# SensorHub.net
KiCad netlist of a schematic drawn in EAGLE
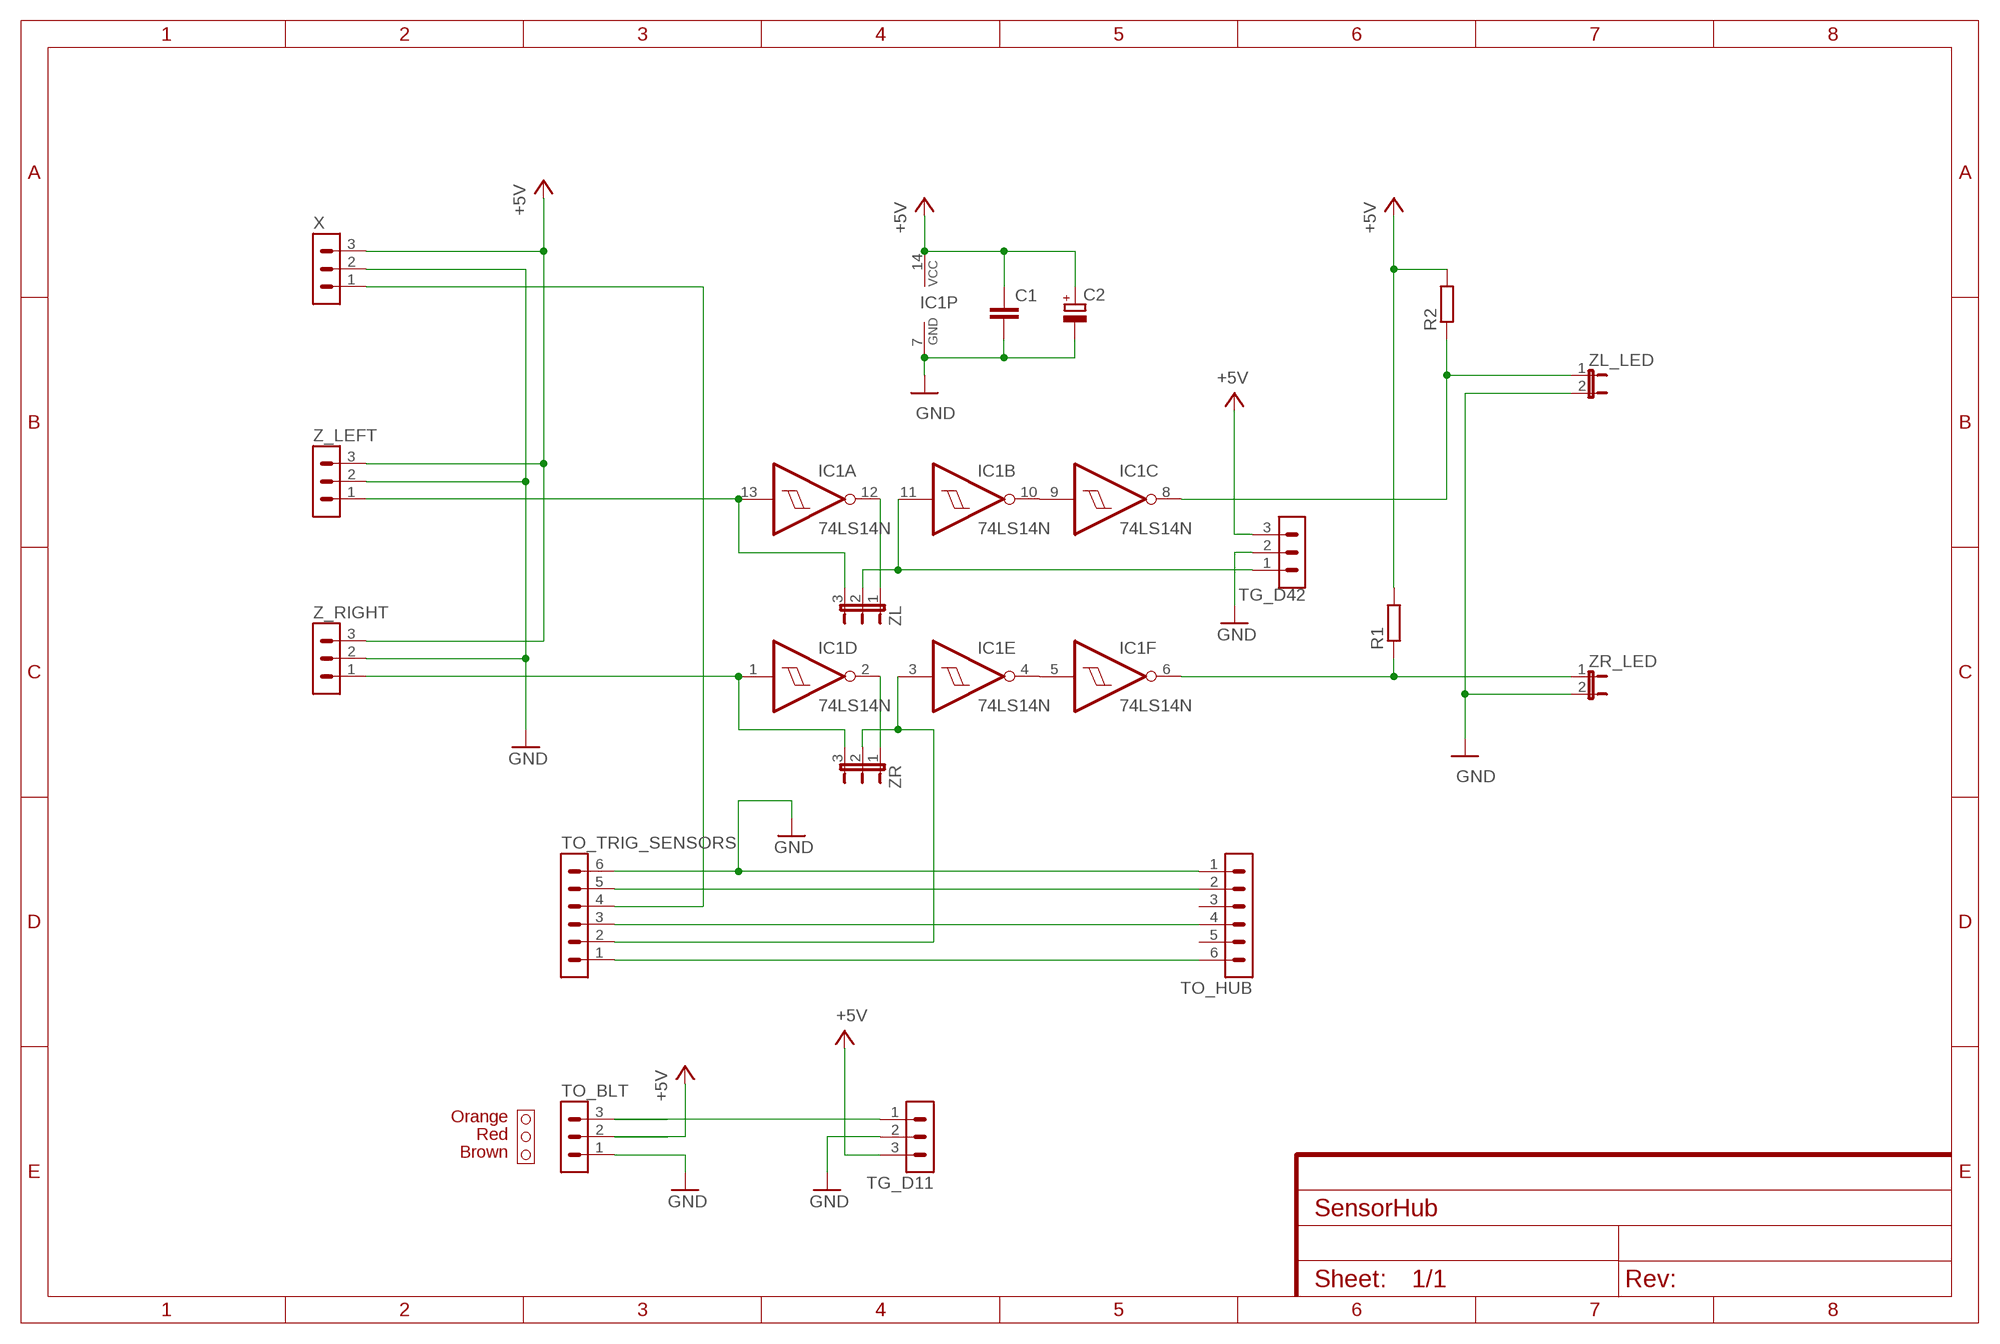
[diagram p0: schematic, sheet 1]

(export (version "E")
  (design (tool "Eeschema 10.0.6"))
  (components
    (comp (ref "C1")
      (value "C-EU050-030X075")
      (footprint "eagle-import:C050-030X075")
      (libsource (lib "eagle-import") (part "C-EU050-030X075"))
    )
    (comp (ref "C2")
      (value "CPOL-EUE3.5-8")
      (footprint "eagle-import:E3,5-8")
      (libsource (lib "eagle-import") (part "CPOL-EUE3.5-8"))
    )
    (comp (ref "IC1")
      (value "74LS14N")
      (footprint "eagle-import:DIL14")
      (libsource (lib "eagle-import") (part "7414NLS"))
    )
    (comp (ref "R1")
      (value "R-EU_0207/10")
      (footprint "eagle-import:0207_10")
      (libsource (lib "eagle-import") (part "R-EU_0207/10"))
    )
    (comp (ref "R2")
      (value "R-EU_0207/10")
      (footprint "eagle-import:0207_10")
      (libsource (lib "eagle-import") (part "R-EU_0207/10"))
    )
    (comp (ref "TG_D11")
      (value "JST-3PTOP")
      (footprint "eagle-import:XH-A-TOP-3P")
      (libsource (lib "eagle-import") (part "JST-3PTOP"))
    )
    (comp (ref "TG_D42")
      (value "JST-3PTOP")
      (footprint "eagle-import:XH-A-TOP-3P")
      (libsource (lib "eagle-import") (part "JST-3PTOP"))
    )
    (comp (ref "TO_BLT")
      (value "JST-3PTOP")
      (footprint "eagle-import:XH-A-TOP-3P")
      (libsource (lib "eagle-import") (part "JST-3PTOP"))
    )
    (comp (ref "TO_HUB")
      (value "JST-6PPH-TOP")
      (footprint "eagle-import:PH-TOP-6P")
      (libsource (lib "eagle-import") (part "JST-6PPH-TOP"))
    )
    (comp (ref "TO_TRIG_SENSORS")
      (value "JST-6PPH-TOP")
      (footprint "eagle-import:PH-TOP-6P")
      (libsource (lib "eagle-import") (part "JST-6PPH-TOP"))
    )
    (comp (ref "X")
      (value "JST-3PTOP")
      (footprint "eagle-import:XH-A-TOP-3P")
      (libsource (lib "eagle-import") (part "JST-3PTOP"))
    )
    (comp (ref "ZL")
      (value "JP2E")
      (footprint "eagle-import:JP2")
      (libsource (lib "eagle-import") (part "JP2E"))
    )
    (comp (ref "ZL_LED")
      (value "ZL LED")
      (footprint "eagle-import:JP1")
      (libsource (lib "eagle-import") (part "JP1E"))
    )
    (comp (ref "ZR")
      (value "JP2E")
      (footprint "eagle-import:JP2")
      (libsource (lib "eagle-import") (part "JP2E"))
    )
    (comp (ref "ZR_LED")
      (value "ZR LED")
      (footprint "eagle-import:JP1")
      (libsource (lib "eagle-import") (part "JP1E"))
    )
    (comp (ref "Z_LEFT")
      (value "JST-3PTOP")
      (footprint "eagle-import:XH-A-TOP-3P")
      (libsource (lib "eagle-import") (part "JST-3PTOP"))
    )
    (comp (ref "Z_RIGHT")
      (value "JST-3PTOP")
      (footprint "eagle-import:XH-A-TOP-3P")
      (libsource (lib "eagle-import") (part "JST-3PTOP"))
    )
  )
  (nets
    (net (code "1") (name "+5V") (class "Default")
      (node (ref "C1") (pin "1") (pinfunction "1_1") (pintype "passive"))
      (node (ref "C2") (pin "+") (pinfunction "+_+") (pintype "passive"))
      (node (ref "IC1") (pin "14") (pinfunction "VCC_14") (pintype "power_in"))
      (node (ref "R1") (pin "2") (pinfunction "2_2") (pintype "passive"))
      (node (ref "R2") (pin "2") (pinfunction "2_2") (pintype "passive"))
      (node (ref "TG_D11") (pin "3") (pinfunction "3_3") (pintype "bidirectional"))
      (node (ref "TG_D42") (pin "3") (pinfunction "3_3") (pintype "bidirectional"))
      (node (ref "TO_BLT") (pin "2") (pinfunction "2_2") (pintype "bidirectional"))
      (node (ref "X") (pin "3") (pinfunction "3_3") (pintype "bidirectional"))
      (node (ref "Z_LEFT") (pin "3") (pinfunction "3_3") (pintype "bidirectional"))
      (node (ref "Z_RIGHT") (pin "3") (pinfunction "3_3") (pintype "bidirectional"))
    )
    (net (code "2") (name "GND") (class "Default")
      (node (ref "C1") (pin "2") (pinfunction "2_2") (pintype "passive"))
      (node (ref "C2") (pin "-") (pinfunction "-_-") (pintype "passive"))
      (node (ref "IC1") (pin "7") (pinfunction "GND_7") (pintype "power_in"))
      (node (ref "TG_D11") (pin "2") (pinfunction "2_2") (pintype "bidirectional"))
      (node (ref "TG_D42") (pin "2") (pinfunction "2_2") (pintype "bidirectional"))
      (node (ref "TO_BLT") (pin "1") (pinfunction "1_1") (pintype "bidirectional"))
      (node (ref "TO_HUB") (pin "1") (pinfunction "1_1") (pintype "bidirectional"))
      (node (ref "TO_TRIG_SENSORS") (pin "6") (pinfunction "6_6") (pintype "bidirectional"))
      (node (ref "X") (pin "2") (pinfunction "2_2") (pintype "bidirectional"))
      (node (ref "ZL_LED") (pin "2") (pinfunction "2_2") (pintype "passive"))
      (node (ref "ZR_LED") (pin "2") (pinfunction "2_2") (pintype "passive"))
      (node (ref "Z_LEFT") (pin "2") (pinfunction "2_2") (pintype "bidirectional"))
      (node (ref "Z_RIGHT") (pin "2") (pinfunction "2_2") (pintype "bidirectional"))
    )
    (net (code "3") (name "Net-(IC1A-I)") (class "Default")
      (node (ref "IC1") (pin "13") (pinfunction "I_13") (pintype "input"))
      (node (ref "ZL") (pin "3") (pinfunction "3_3") (pintype "passive"))
      (node (ref "Z_LEFT") (pin "1") (pinfunction "1_1") (pintype "bidirectional"))
    )
    (net (code "4") (name "Net-(IC1A-O)") (class "Default")
      (node (ref "IC1") (pin "12") (pinfunction "O_12") (pintype "output"))
      (node (ref "ZL") (pin "1") (pinfunction "1_1") (pintype "passive"))
    )
    (net (code "5") (name "Net-(IC1B-I)") (class "Default")
      (node (ref "IC1") (pin "11") (pinfunction "I_11") (pintype "input"))
      (node (ref "TG_D42") (pin "1") (pinfunction "1_1") (pintype "bidirectional"))
      (node (ref "ZL") (pin "2") (pinfunction "2_2") (pintype "passive"))
    )
    (net (code "6") (name "Net-(IC1B-O)") (class "Default")
      (node (ref "IC1") (pin "10") (pinfunction "O_10") (pintype "output"))
      (node (ref "IC1") (pin "9") (pinfunction "I_9") (pintype "input"))
    )
    (net (code "7") (name "Net-(IC1C-O)") (class "Default")
      (node (ref "IC1") (pin "8") (pinfunction "O_8") (pintype "output"))
      (node (ref "R2") (pin "1") (pinfunction "1_1") (pintype "passive"))
      (node (ref "ZL_LED") (pin "1") (pinfunction "1_1") (pintype "passive"))
    )
    (net (code "8") (name "Net-(IC1D-I)") (class "Default")
      (node (ref "IC1") (pin "1") (pinfunction "I_1") (pintype "input"))
      (node (ref "ZR") (pin "3") (pinfunction "3_3") (pintype "passive"))
      (node (ref "Z_RIGHT") (pin "1") (pinfunction "1_1") (pintype "bidirectional"))
    )
    (net (code "9") (name "Net-(IC1D-O)") (class "Default")
      (node (ref "IC1") (pin "2") (pinfunction "O_2") (pintype "output"))
      (node (ref "ZR") (pin "1") (pinfunction "1_1") (pintype "passive"))
    )
    (net (code "10") (name "Net-(IC1E-I)") (class "Default")
      (node (ref "IC1") (pin "3") (pinfunction "I_3") (pintype "input"))
      (node (ref "TO_TRIG_SENSORS") (pin "2") (pinfunction "2_2") (pintype "bidirectional"))
      (node (ref "ZR") (pin "2") (pinfunction "2_2") (pintype "passive"))
    )
    (net (code "11") (name "Net-(IC1E-O)") (class "Default")
      (node (ref "IC1") (pin "4") (pinfunction "O_4") (pintype "output"))
      (node (ref "IC1") (pin "5") (pinfunction "I_5") (pintype "input"))
    )
    (net (code "12") (name "Net-(IC1F-O)") (class "Default")
      (node (ref "IC1") (pin "6") (pinfunction "O_6") (pintype "output"))
      (node (ref "R1") (pin "1") (pinfunction "1_1") (pintype "passive"))
      (node (ref "ZR_LED") (pin "1") (pinfunction "1_1") (pintype "passive"))
    )
    (net (code "13") (name "Net-(TG_D11-Pad1)") (class "Default")
      (node (ref "TG_D11") (pin "1") (pinfunction "1_1") (pintype "bidirectional"))
      (node (ref "TO_BLT") (pin "3") (pinfunction "3_3") (pintype "bidirectional"))
    )
    (net (code "14") (name "Net-(TO_HUB-Pad2)") (class "Default")
      (node (ref "TO_HUB") (pin "2") (pinfunction "2_2") (pintype "bidirectional"))
      (node (ref "TO_TRIG_SENSORS") (pin "5") (pinfunction "5_5") (pintype "bidirectional"))
    )
    (net (code "15") (name "Net-(TO_HUB-Pad4)") (class "Default")
      (node (ref "TO_HUB") (pin "4") (pinfunction "4_4") (pintype "bidirectional"))
      (node (ref "TO_TRIG_SENSORS") (pin "3") (pinfunction "3_3") (pintype "bidirectional"))
    )
    (net (code "16") (name "Net-(TO_HUB-Pad6)") (class "Default")
      (node (ref "TO_HUB") (pin "6") (pinfunction "6_6") (pintype "bidirectional"))
      (node (ref "TO_TRIG_SENSORS") (pin "1") (pinfunction "1_1") (pintype "bidirectional"))
    )
    (net (code "17") (name "Net-(TO_TRIG_SENSORS-Pad4)") (class "Default")
      (node (ref "TO_TRIG_SENSORS") (pin "4") (pinfunction "4_4") (pintype "bidirectional"))
      (node (ref "X") (pin "1") (pinfunction "1_1") (pintype "bidirectional"))
    )
    (net (code "18") (name "unconnected-(TO_HUB-Pad3)") (class "Default")
      (node (ref "TO_HUB") (pin "3") (pinfunction "3_3") (pintype "bidirectional"))
    )
    (net (code "19") (name "unconnected-(TO_HUB-Pad5)") (class "Default")
      (node (ref "TO_HUB") (pin "5") (pinfunction "5_5") (pintype "bidirectional"))
    )
  )
)
